# tedy.net
KiCad netlist of a schematic drawn in EAGLE
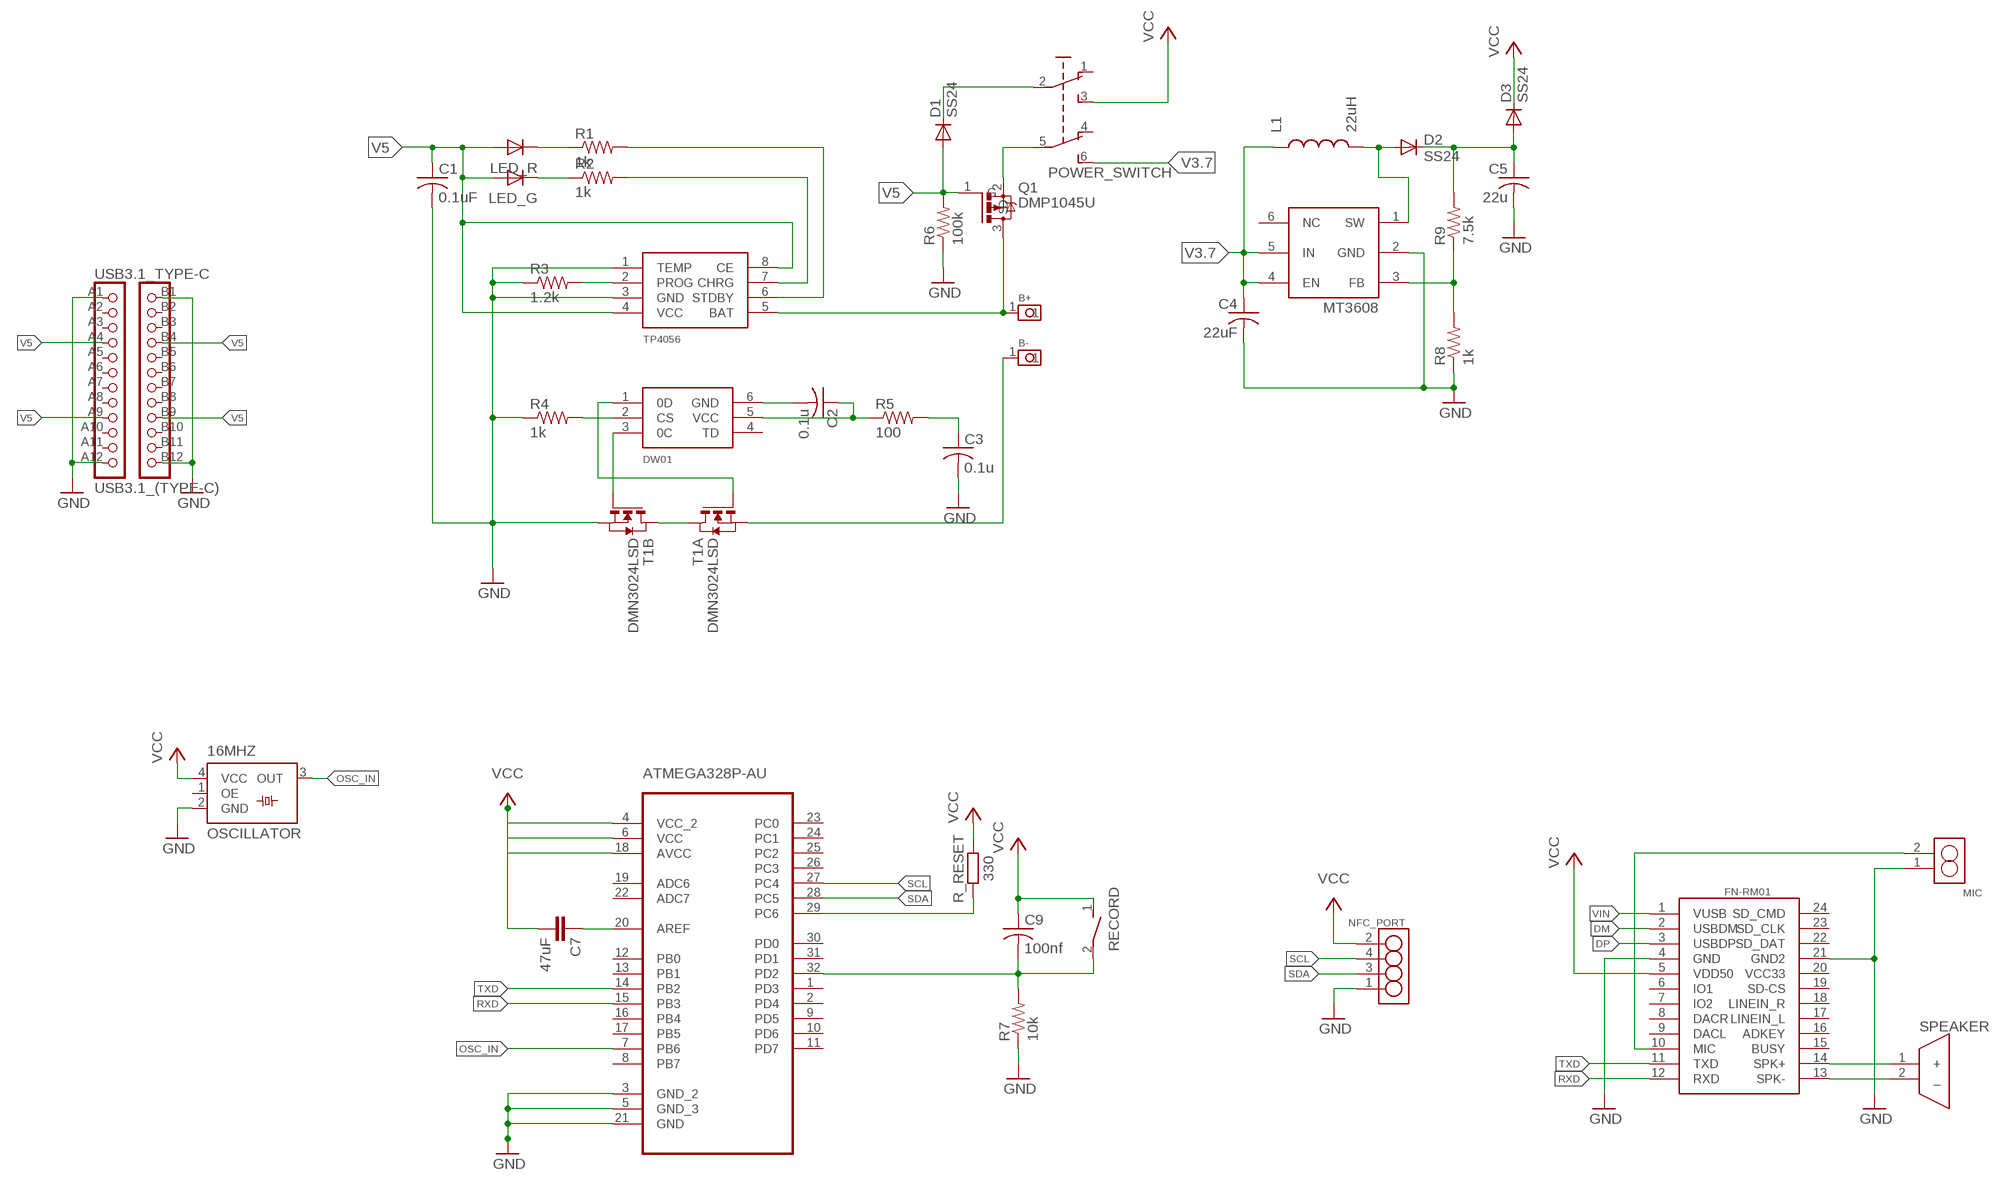
[diagram p0: schematic, sheet 1]

(export (version "E")
  (design (tool "Eeschema 10.0.6"))
  (components
    (comp (ref "16MHZ")
      (value "OSCILLATOR")
      (footprint "eagle-import:OSCILLATOR_(3.2_2.5)")
      (libsource (lib "eagle-import") (part "OSCILLATOR"))
    )
    (comp (ref "ATMEGA328P-AU")
      (value "ATMEGA328P-AU")
      (footprint "eagle-import:QFP80P900X900X120-32N")
      (libsource (lib "eagle-import") (part "ATMEGA328P-AU"))
    )
    (comp (ref "B+")
      (value "B+")
      (footprint "eagle-import:PIN_1")
      (libsource (lib "eagle-import") (part "PIN_1"))
    )
    (comp (ref "B-")
      (value "B-")
      (footprint "eagle-import:PIN_1")
      (libsource (lib "eagle-import") (part "PIN_1"))
    )
    (comp (ref "C1")
      (value "0.1uF")
      (footprint "eagle-import:C0805")
      (libsource (lib "eagle-import") (part "resistor_348_C-USC0805"))
    )
    (comp (ref "C2")
      (value "0.1u")
      (footprint "eagle-import:C0805")
      (libsource (lib "eagle-import") (part "resistor_348_C-USC0805"))
    )
    (comp (ref "C3")
      (value "0.1u")
      (footprint "eagle-import:C0805")
      (libsource (lib "eagle-import") (part "resistor_348_C-USC0805"))
    )
    (comp (ref "C4")
      (value "22uF")
      (footprint "eagle-import:C0805")
      (libsource (lib "eagle-import") (part "resistor_348_C-USC0805"))
    )
    (comp (ref "C5")
      (value "22u")
      (footprint "eagle-import:C0805")
      (libsource (lib "eagle-import") (part "resistor_348_C-USC0805"))
    )
    (comp (ref "C7")
      (value "47uF")
      (footprint "eagle-import:C0805")
      (libsource (lib "eagle-import") (part "C-EUC0805"))
    )
    (comp (ref "C9")
      (value "100nf")
      (footprint "eagle-import:C0805K")
      (libsource (lib "eagle-import") (part "C-USC0805K"))
    )
    (comp (ref "D1")
      (value "SS24")
      (footprint "eagle-import:SS24")
      (libsource (lib "eagle-import") (part "SS24"))
    )
    (comp (ref "D2")
      (value "SS24")
      (footprint "eagle-import:SS24")
      (libsource (lib "eagle-import") (part "SS24"))
    )
    (comp (ref "D3")
      (value "SS24")
      (footprint "eagle-import:SS24")
      (libsource (lib "eagle-import") (part "SS24"))
    )
    (comp (ref "DW01")
      (value "DW01")
      (footprint "eagle-import:SOT23-6")
      (libsource (lib "eagle-import") (part "DW01"))
    )
    (comp (ref "FN-RM01")
      (value "FN-RM01")
      (footprint "eagle-import:FN-RM01")
      (libsource (lib "eagle-import") (part "FN-RM01"))
    )
    (comp (ref "L1")
      (value "22uH")
      (footprint "eagle-import:4D28")
      (libsource (lib "eagle-import") (part "4D28"))
    )
    (comp (ref "LED_")
      (value "2_COLOUR_LED")
      (footprint "eagle-import:2_COLOUR_LED")
      (libsource (lib "eagle-import") (part "2_COLOUR_LED"))
    )
    (comp (ref "MIC")
      (value "CONNECTOR_1.5MM_THROUGH_HOLE_(2_PIN)")
      (footprint "eagle-import:CONNECTOR_1.5MM_THROUGH_HOLE_(2_PIN)")
      (libsource (lib "eagle-import") (part "CONNECTOR_1.5MM_THROUGH_HOLE_(2_PIN)"))
    )
    (comp (ref "MT3608")
      (value "MT3608")
      (footprint "eagle-import:SOT23-6")
      (libsource (lib "eagle-import") (part "MT3608"))
    )
    (comp (ref "NFC_PORT")
      (value "PN532")
      (footprint "eagle-import:PN532")
      (libsource (lib "eagle-import") (part "PN532"))
    )
    (comp (ref "POWER_SWITCH")
      (value "6PIN_SWITCH")
      (footprint "eagle-import:6PIN_SWITCH")
      (libsource (lib "eagle-import") (part "6PIN_SWITCH"))
    )
    (comp (ref "Q1")
      (value "DMP1045U")
      (footprint "eagle-import:SOT23-3")
      (libsource (lib "eagle-import") (part "DMP1045U"))
    )
    (comp (ref "R1")
      (value "1k")
      (footprint "eagle-import:R0805")
      (libsource (lib "eagle-import") (part "resistor_348_R-US_R0805"))
    )
    (comp (ref "R2")
      (value "1k")
      (footprint "eagle-import:R0805")
      (libsource (lib "eagle-import") (part "resistor_348_R-US_R0805"))
    )
    (comp (ref "R3")
      (value "1.2k")
      (footprint "eagle-import:R0805")
      (libsource (lib "eagle-import") (part "resistor_348_R-US_R0805"))
    )
    (comp (ref "R4")
      (value "1k")
      (footprint "eagle-import:R0805")
      (libsource (lib "eagle-import") (part "resistor_348_R-US_R0805"))
    )
    (comp (ref "R5")
      (value "100")
      (footprint "eagle-import:R0805")
      (libsource (lib "eagle-import") (part "resistor_348_R-US_R0805"))
    )
    (comp (ref "R6")
      (value "100k")
      (footprint "eagle-import:R0805")
      (libsource (lib "eagle-import") (part "resistor_348_R-US_R0805"))
    )
    (comp (ref "R7")
      (value "10k")
      (footprint "eagle-import:R0805")
      (libsource (lib "eagle-import") (part "R-US_R0805"))
    )
    (comp (ref "R8")
      (value "1k")
      (footprint "eagle-import:R0805")
      (libsource (lib "eagle-import") (part "resistor_348_R-US_R0805"))
    )
    (comp (ref "R9")
      (value "7.5k")
      (footprint "eagle-import:R0805")
      (libsource (lib "eagle-import") (part "resistor_348_R-US_R0805"))
    )
    (comp (ref "RECORD")
      (value "PUSH_BUTTON(SIDE)")
      (footprint "eagle-import:PUSH_BUTTON(SIDE)")
      (libsource (lib "eagle-import") (part "PUSH_BUTTON(SIDE)"))
    )
    (comp (ref "R_RESET")
      (value "330")
      (footprint "eagle-import:M0805")
      (libsource (lib "eagle-import") (part "R-EU_M0805"))
    )
    (comp (ref "SPEAKER")
      (value "SPEAKER")
      (footprint "eagle-import:SPEAKER")
      (libsource (lib "eagle-import") (part "SPEAKER"))
    )
    (comp (ref "T1")
      (value "DMN3024LSD")
      (footprint "eagle-import:TSSOP-8")
      (libsource (lib "eagle-import") (part "DMN3024LSD"))
    )
    (comp (ref "TP4056")
      (value "TP4056")
      (footprint "eagle-import:SOP-8")
      (libsource (lib "eagle-import") (part "TP4056"))
    )
    (comp (ref "USB3.1_TYPE-C")
      (value "USB3.1_(TYPE-C)")
      (footprint "eagle-import:USB3.1_(TYPE-C)")
      (libsource (lib "eagle-import") (part "USB3.1_(TYPE-C)"))
    )
  )
  (nets
    (net (code "1") (name "DM") (class "Default")
      (node (ref "FN-RM01") (pin "2") (pinfunction "USBDM_2") (pintype "bidirectional"))
    )
    (net (code "2") (name "DP") (class "Default")
      (node (ref "FN-RM01") (pin "3") (pinfunction "USBDP_3") (pintype "bidirectional"))
    )
    (net (code "3") (name "GND") (class "Default")
      (node (ref "16MHZ") (pin "2") (pinfunction "GND_2") (pintype "power_in"))
      (node (ref "ATMEGA328P-AU") (pin "21") (pinfunction "GND_21") (pintype "passive"))
      (node (ref "ATMEGA328P-AU") (pin "3") (pinfunction "GND_2_3") (pintype "passive"))
      (node (ref "ATMEGA328P-AU") (pin "5") (pinfunction "GND_3_5") (pintype "passive"))
      (node (ref "C1") (pin "2") (pinfunction "2_2") (pintype "passive"))
      (node (ref "C3") (pin "2") (pinfunction "2_2") (pintype "passive"))
      (node (ref "C4") (pin "2") (pinfunction "2_2") (pintype "passive"))
      (node (ref "C5") (pin "2") (pinfunction "2_2") (pintype "passive"))
      (node (ref "FN-RM01") (pin "21") (pinfunction "GND2_21") (pintype "bidirectional"))
      (node (ref "FN-RM01") (pin "4") (pinfunction "GND_4") (pintype "bidirectional"))
      (node (ref "MIC") (pin "1") (pinfunction "1_1") (pintype "bidirectional"))
      (node (ref "MT3608") (pin "2") (pinfunction "GND_2") (pintype "bidirectional"))
      (node (ref "NFC_PORT") (pin "1") (pinfunction "4_1") (pintype "bidirectional"))
      (node (ref "R3") (pin "1") (pinfunction "1_1") (pintype "passive"))
      (node (ref "R4") (pin "1") (pinfunction "1_1") (pintype "passive"))
      (node (ref "R6") (pin "1") (pinfunction "1_1") (pintype "passive"))
      (node (ref "R7") (pin "1") (pinfunction "1_1") (pintype "passive"))
      (node (ref "R8") (pin "1") (pinfunction "1_1") (pintype "passive"))
      (node (ref "T1") (pin "6") (pinfunction "S_6") (pintype "passive"))
      (node (ref "T1") (pin "7") (pinfunction "S_7") (pintype "passive"))
      (node (ref "TP4056") (pin "1") (pinfunction "TEMP_1") (pintype "bidirectional"))
      (node (ref "TP4056") (pin "3") (pinfunction "GND_3") (pintype "bidirectional"))
      (node (ref "USB3.1_TYPE-C") (pin "A1") (pinfunction "A1_A1") (pintype "passive"))
      (node (ref "USB3.1_TYPE-C") (pin "A12") (pinfunction "A12_A12") (pintype "passive"))
      (node (ref "USB3.1_TYPE-C") (pin "B1") (pinfunction "B1_B1") (pintype "passive"))
      (node (ref "USB3.1_TYPE-C") (pin "B12") (pinfunction "B12_B12") (pintype "passive"))
    )
    (net (code "4") (name "Net-(ATMEGA328P-AU-AREF)") (class "Default")
      (node (ref "ATMEGA328P-AU") (pin "20") (pinfunction "AREF_20") (pintype "input"))
      (node (ref "C7") (pin "1") (pinfunction "1_1") (pintype "passive"))
    )
    (net (code "5") (name "Net-(ATMEGA328P-AU-PC6)") (class "Default")
      (node (ref "ATMEGA328P-AU") (pin "29") (pinfunction "PC6_29") (pintype "bidirectional"))
      (node (ref "R_RESET") (pin "2") (pinfunction "2_2") (pintype "passive"))
    )
    (net (code "6") (name "Net-(ATMEGA328P-AU-PD2)") (class "Default")
      (node (ref "ATMEGA328P-AU") (pin "32") (pinfunction "PD2_32") (pintype "bidirectional"))
      (node (ref "C9") (pin "2") (pinfunction "2_2") (pintype "passive"))
      (node (ref "R7") (pin "2") (pinfunction "2_2") (pintype "passive"))
      (node (ref "RECORD") (pin "2") (pinfunction "2_2") (pintype "passive"))
    )
    (net (code "7") (name "Net-(B--Pad1)") (class "Default")
      (node (ref "B-") (pin "1") (pinfunction "1_1") (pintype "bidirectional"))
      (node (ref "T1") (pin "2") (pinfunction "S_2") (pintype "passive"))
      (node (ref "T1") (pin "3") (pinfunction "S_3") (pintype "passive"))
    )
    (net (code "8") (name "Net-(C3-Pad1)") (class "Default")
      (node (ref "C3") (pin "1") (pinfunction "1_1") (pintype "passive"))
      (node (ref "R5") (pin "2") (pinfunction "2_2") (pintype "passive"))
    )
    (net (code "9") (name "Net-(D1-C)") (class "Default")
      (node (ref "D1") (pin "2") (pinfunction "C_2") (pintype "passive"))
      (node (ref "POWER_SWITCH") (pin "2") (pinfunction "P_2") (pintype "passive"))
    )
    (net (code "10") (name "Net-(D2-A)") (class "Default")
      (node (ref "D2") (pin "1") (pinfunction "A_1") (pintype "passive"))
      (node (ref "L1") (pin "P$2") (pinfunction "2_P$2") (pintype "passive"))
      (node (ref "MT3608") (pin "1") (pinfunction "SW_1") (pintype "bidirectional"))
    )
    (net (code "11") (name "Net-(D2-C)") (class "Default")
      (node (ref "C5") (pin "1") (pinfunction "1_1") (pintype "passive"))
      (node (ref "D2") (pin "2") (pinfunction "C_2") (pintype "passive"))
      (node (ref "D3") (pin "1") (pinfunction "A_1") (pintype "passive"))
      (node (ref "R9") (pin "2") (pinfunction "2_2") (pintype "passive"))
    )
    (net (code "12") (name "Net-(DW01-0C)") (class "Default")
      (node (ref "DW01") (pin "3") (pinfunction "0C_3") (pintype "bidirectional"))
      (node (ref "T1") (pin "5") (pinfunction "G_5") (pintype "passive"))
    )
    (net (code "13") (name "Net-(DW01-0D)") (class "Default")
      (node (ref "DW01") (pin "1") (pinfunction "0D_1") (pintype "bidirectional"))
      (node (ref "T1") (pin "4") (pinfunction "G_4") (pintype "passive"))
    )
    (net (code "14") (name "Net-(DW01-CS)") (class "Default")
      (node (ref "DW01") (pin "2") (pinfunction "CS_2") (pintype "bidirectional"))
      (node (ref "R4") (pin "2") (pinfunction "2_2") (pintype "passive"))
    )
    (net (code "15") (name "Net-(DW01-GND)") (class "Default")
      (node (ref "C2") (pin "2") (pinfunction "2_2") (pintype "passive"))
      (node (ref "DW01") (pin "6") (pinfunction "GND_6") (pintype "bidirectional"))
    )
    (net (code "16") (name "Net-(DW01-VCC)") (class "Default")
      (node (ref "C2") (pin "1") (pinfunction "1_1") (pintype "passive"))
      (node (ref "DW01") (pin "5") (pinfunction "VCC_5") (pintype "bidirectional"))
      (node (ref "R5") (pin "1") (pinfunction "1_1") (pintype "passive"))
    )
    (net (code "17") (name "Net-(FN-RM01-MIC)") (class "Default")
      (node (ref "FN-RM01") (pin "10") (pinfunction "MIC_10") (pintype "bidirectional"))
      (node (ref "MIC") (pin "2") (pinfunction "2_2") (pintype "bidirectional"))
    )
    (net (code "18") (name "Net-(FN-RM01-SPK+)") (class "Default")
      (node (ref "FN-RM01") (pin "14") (pinfunction "SPK+_14") (pintype "bidirectional"))
      (node (ref "SPEAKER") (pin "1") (pinfunction "+_1") (pintype "bidirectional"))
    )
    (net (code "19") (name "Net-(FN-RM01-SPK-)") (class "Default")
      (node (ref "FN-RM01") (pin "13") (pinfunction "SPK-_13") (pintype "bidirectional"))
      (node (ref "SPEAKER") (pin "2") (pinfunction "__2") (pintype "bidirectional"))
    )
    (net (code "20") (name "Net-(LED_-Pad1)") (class "Default")
      (node (ref "LED_") (pin "1") (pinfunction "1_1") (pintype "passive"))
      (node (ref "R1") (pin "1") (pinfunction "1_1") (pintype "passive"))
    )
    (net (code "21") (name "Net-(LED_A-1)") (class "Default")
      (node (ref "LED_") (pin "3") (pinfunction "1_3") (pintype "passive"))
      (node (ref "R2") (pin "1") (pinfunction "1_1") (pintype "passive"))
    )
    (net (code "22") (name "Net-(MT3608-FB)") (class "Default")
      (node (ref "MT3608") (pin "3") (pinfunction "FB_3") (pintype "bidirectional"))
      (node (ref "R8") (pin "2") (pinfunction "2_2") (pintype "passive"))
      (node (ref "R9") (pin "1") (pinfunction "1_1") (pintype "passive"))
    )
    (net (code "23") (name "Net-(Q1-D)") (class "Default")
      (node (ref "B+") (pin "1") (pinfunction "1_1") (pintype "bidirectional"))
      (node (ref "Q1") (pin "3") (pinfunction "D_3") (pintype "bidirectional"))
      (node (ref "TP4056") (pin "5") (pinfunction "BAT_5") (pintype "bidirectional"))
    )
    (net (code "24") (name "Net-(T1A-D)") (class "Default")
      (node (ref "T1") (pin "1") (pinfunction "D_1") (pintype "passive"))
      (node (ref "T1") (pin "8") (pinfunction "D_8") (pintype "passive"))
    )
    (net (code "25") (name "Net-(TP4056-CHRG)") (class "Default")
      (node (ref "R2") (pin "2") (pinfunction "2_2") (pintype "passive"))
      (node (ref "TP4056") (pin "7") (pinfunction "CHRG_7") (pintype "bidirectional"))
    )
    (net (code "26") (name "Net-(TP4056-PROG)") (class "Default")
      (node (ref "R3") (pin "2") (pinfunction "2_2") (pintype "passive"))
      (node (ref "TP4056") (pin "2") (pinfunction "PROG_2") (pintype "bidirectional"))
    )
    (net (code "27") (name "Net-(TP4056-STDBY)") (class "Default")
      (node (ref "R1") (pin "2") (pinfunction "2_2") (pintype "passive"))
      (node (ref "TP4056") (pin "6") (pinfunction "STDBY_6") (pintype "bidirectional"))
    )
    (net (code "28") (name "OSC_IN") (class "Default")
      (node (ref "16MHZ") (pin "3") (pinfunction "OUT_3") (pintype "output"))
      (node (ref "ATMEGA328P-AU") (pin "7") (pinfunction "PB6_7") (pintype "bidirectional"))
    )
    (net (code "29") (name "RXD") (class "Default")
      (node (ref "ATMEGA328P-AU") (pin "15") (pinfunction "PB3_15") (pintype "bidirectional"))
      (node (ref "FN-RM01") (pin "12") (pinfunction "RXD_12") (pintype "bidirectional"))
    )
    (net (code "30") (name "SCL") (class "Default")
      (node (ref "ATMEGA328P-AU") (pin "27") (pinfunction "PC4_27") (pintype "bidirectional"))
      (node (ref "NFC_PORT") (pin "4") (pinfunction "2_4") (pintype "bidirectional"))
    )
    (net (code "31") (name "SDA") (class "Default")
      (node (ref "ATMEGA328P-AU") (pin "28") (pinfunction "PC5_28") (pintype "bidirectional"))
      (node (ref "NFC_PORT") (pin "3") (pinfunction "3_3") (pintype "bidirectional"))
    )
    (net (code "32") (name "TXD") (class "Default")
      (node (ref "ATMEGA328P-AU") (pin "14") (pinfunction "PB2_14") (pintype "bidirectional"))
      (node (ref "FN-RM01") (pin "11") (pinfunction "TXD_11") (pintype "bidirectional"))
    )
    (net (code "33") (name "V3.7") (class "Default")
      (node (ref "C4") (pin "1") (pinfunction "1_1") (pintype "passive"))
      (node (ref "L1") (pin "P$1") (pinfunction "1_P$1") (pintype "passive"))
      (node (ref "MT3608") (pin "4") (pinfunction "EN_4") (pintype "bidirectional"))
      (node (ref "MT3608") (pin "5") (pinfunction "IN_5") (pintype "bidirectional"))
      (node (ref "POWER_SWITCH") (pin "5") (pinfunction "P1_5") (pintype "passive"))
      (node (ref "POWER_SWITCH") (pin "6") (pinfunction "S1_6") (pintype "passive"))
      (node (ref "Q1") (pin "2") (pinfunction "S_2") (pintype "bidirectional"))
    )
    (net (code "34") (name "V5") (class "Default")
      (node (ref "C1") (pin "1") (pinfunction "1_1") (pintype "passive"))
      (node (ref "D1") (pin "1") (pinfunction "A_1") (pintype "passive"))
      (node (ref "LED_") (pin "2") (pinfunction "2_2") (pintype "passive"))
      (node (ref "LED_") (pin "4") (pinfunction "2_4") (pintype "passive"))
      (node (ref "Q1") (pin "1") (pinfunction "G_1") (pintype "bidirectional"))
      (node (ref "R6") (pin "2") (pinfunction "2_2") (pintype "passive"))
      (node (ref "TP4056") (pin "4") (pinfunction "VCC_4") (pintype "bidirectional"))
      (node (ref "TP4056") (pin "8") (pinfunction "CE_8") (pintype "bidirectional"))
      (node (ref "USB3.1_TYPE-C") (pin "A4") (pinfunction "A4_A4") (pintype "passive"))
      (node (ref "USB3.1_TYPE-C") (pin "A9") (pinfunction "A9_A9") (pintype "passive"))
      (node (ref "USB3.1_TYPE-C") (pin "B4") (pinfunction "B4_B4") (pintype "passive"))
      (node (ref "USB3.1_TYPE-C") (pin "B9") (pinfunction "B9_B9") (pintype "passive"))
    )
    (net (code "35") (name "VCC") (class "Default")
      (node (ref "16MHZ") (pin "4") (pinfunction "VCC_4") (pintype "power_in"))
      (node (ref "ATMEGA328P-AU") (pin "18") (pinfunction "AVCC_18") (pintype "power_in"))
      (node (ref "ATMEGA328P-AU") (pin "4") (pinfunction "VCC_2_4") (pintype "power_in"))
      (node (ref "ATMEGA328P-AU") (pin "6") (pinfunction "VCC_6") (pintype "power_in"))
      (node (ref "C7") (pin "2") (pinfunction "2_2") (pintype "passive"))
      (node (ref "C9") (pin "1") (pinfunction "1_1") (pintype "passive"))
      (node (ref "D3") (pin "2") (pinfunction "C_2") (pintype "passive"))
      (node (ref "FN-RM01") (pin "5") (pinfunction "VDD50_5") (pintype "bidirectional"))
      (node (ref "NFC_PORT") (pin "2") (pinfunction "1_2") (pintype "bidirectional"))
      (node (ref "POWER_SWITCH") (pin "3") (pinfunction "S_3") (pintype "passive"))
      (node (ref "RECORD") (pin "1") (pinfunction "1_1") (pintype "passive"))
      (node (ref "R_RESET") (pin "1") (pinfunction "1_1") (pintype "passive"))
    )
    (net (code "36") (name "VIN") (class "Default")
      (node (ref "FN-RM01") (pin "1") (pinfunction "VUSB_1") (pintype "bidirectional"))
    )
    (net (code "37") (name "unconnected-(16MHZ-OE-Pad1)") (class "Default")
      (node (ref "16MHZ") (pin "1") (pinfunction "OE_1") (pintype "input"))
    )
    (net (code "38") (name "unconnected-(ATMEGA328P-AU-ADC6-Pad19)") (class "Default")
      (node (ref "ATMEGA328P-AU") (pin "19") (pinfunction "ADC6_19") (pintype "input"))
    )
    (net (code "39") (name "unconnected-(ATMEGA328P-AU-ADC7-Pad22)") (class "Default")
      (node (ref "ATMEGA328P-AU") (pin "22") (pinfunction "ADC7_22") (pintype "input"))
    )
    (net (code "40") (name "unconnected-(ATMEGA328P-AU-PB0-Pad12)") (class "Default")
      (node (ref "ATMEGA328P-AU") (pin "12") (pinfunction "PB0_12") (pintype "bidirectional"))
    )
    (net (code "41") (name "unconnected-(ATMEGA328P-AU-PB1-Pad13)") (class "Default")
      (node (ref "ATMEGA328P-AU") (pin "13") (pinfunction "PB1_13") (pintype "bidirectional"))
    )
    (net (code "42") (name "unconnected-(ATMEGA328P-AU-PB4-Pad16)") (class "Default")
      (node (ref "ATMEGA328P-AU") (pin "16") (pinfunction "PB4_16") (pintype "bidirectional"))
    )
    (net (code "43") (name "unconnected-(ATMEGA328P-AU-PB5-Pad17)") (class "Default")
      (node (ref "ATMEGA328P-AU") (pin "17") (pinfunction "PB5_17") (pintype "bidirectional"))
    )
    (net (code "44") (name "unconnected-(ATMEGA328P-AU-PB7-Pad8)") (class "Default")
      (node (ref "ATMEGA328P-AU") (pin "8") (pinfunction "PB7_8") (pintype "bidirectional"))
    )
    (net (code "45") (name "unconnected-(ATMEGA328P-AU-PC0-Pad23)") (class "Default")
      (node (ref "ATMEGA328P-AU") (pin "23") (pinfunction "PC0_23") (pintype "bidirectional"))
    )
    (net (code "46") (name "unconnected-(ATMEGA328P-AU-PC1-Pad24)") (class "Default")
      (node (ref "ATMEGA328P-AU") (pin "24") (pinfunction "PC1_24") (pintype "bidirectional"))
    )
    (net (code "47") (name "unconnected-(ATMEGA328P-AU-PC2-Pad25)") (class "Default")
      (node (ref "ATMEGA328P-AU") (pin "25") (pinfunction "PC2_25") (pintype "bidirectional"))
    )
    (net (code "48") (name "unconnected-(ATMEGA328P-AU-PC3-Pad26)") (class "Default")
      (node (ref "ATMEGA328P-AU") (pin "26") (pinfunction "PC3_26") (pintype "bidirectional"))
    )
    (net (code "49") (name "unconnected-(ATMEGA328P-AU-PD0-Pad30)") (class "Default")
      (node (ref "ATMEGA328P-AU") (pin "30") (pinfunction "PD0_30") (pintype "bidirectional"))
    )
    (net (code "50") (name "unconnected-(ATMEGA328P-AU-PD1-Pad31)") (class "Default")
      (node (ref "ATMEGA328P-AU") (pin "31") (pinfunction "PD1_31") (pintype "bidirectional"))
    )
    (net (code "51") (name "unconnected-(ATMEGA328P-AU-PD3-Pad1)") (class "Default")
      (node (ref "ATMEGA328P-AU") (pin "1") (pinfunction "PD3_1") (pintype "bidirectional"))
    )
    (net (code "52") (name "unconnected-(ATMEGA328P-AU-PD4-Pad2)") (class "Default")
      (node (ref "ATMEGA328P-AU") (pin "2") (pinfunction "PD4_2") (pintype "bidirectional"))
    )
    (net (code "53") (name "unconnected-(ATMEGA328P-AU-PD5-Pad9)") (class "Default")
      (node (ref "ATMEGA328P-AU") (pin "9") (pinfunction "PD5_9") (pintype "bidirectional"))
    )
    (net (code "54") (name "unconnected-(ATMEGA328P-AU-PD6-Pad10)") (class "Default")
      (node (ref "ATMEGA328P-AU") (pin "10") (pinfunction "PD6_10") (pintype "bidirectional"))
    )
    (net (code "55") (name "unconnected-(ATMEGA328P-AU-PD7-Pad11)") (class "Default")
      (node (ref "ATMEGA328P-AU") (pin "11") (pinfunction "PD7_11") (pintype "bidirectional"))
    )
    (net (code "56") (name "unconnected-(DW01-TD-Pad4)") (class "Default")
      (node (ref "DW01") (pin "4") (pinfunction "TD_4") (pintype "bidirectional"))
    )
    (net (code "57") (name "unconnected-(FN-RM01-ADKEY-Pad16)") (class "Default")
      (node (ref "FN-RM01") (pin "16") (pinfunction "ADKEY_16") (pintype "bidirectional"))
    )
    (net (code "58") (name "unconnected-(FN-RM01-BUSY-Pad15)") (class "Default")
      (node (ref "FN-RM01") (pin "15") (pinfunction "BUSY_15") (pintype "bidirectional"))
    )
    (net (code "59") (name "unconnected-(FN-RM01-DACL-Pad9)") (class "Default")
      (node (ref "FN-RM01") (pin "9") (pinfunction "DACL_9") (pintype "bidirectional"))
    )
    (net (code "60") (name "unconnected-(FN-RM01-DACR-Pad8)") (class "Default")
      (node (ref "FN-RM01") (pin "8") (pinfunction "DACR_8") (pintype "bidirectional"))
    )
    (net (code "61") (name "unconnected-(FN-RM01-IO1-Pad6)") (class "Default")
      (node (ref "FN-RM01") (pin "6") (pinfunction "IO1_6") (pintype "bidirectional"))
    )
    (net (code "62") (name "unconnected-(FN-RM01-IO2-Pad7)") (class "Default")
      (node (ref "FN-RM01") (pin "7") (pinfunction "IO2_7") (pintype "bidirectional"))
    )
    (net (code "63") (name "unconnected-(FN-RM01-LINEIN_L-Pad17)") (class "Default")
      (node (ref "FN-RM01") (pin "17") (pinfunction "LINEIN_L_17") (pintype "bidirectional"))
    )
    (net (code "64") (name "unconnected-(FN-RM01-LINEIN_R-Pad18)") (class "Default")
      (node (ref "FN-RM01") (pin "18") (pinfunction "LINEIN_R_18") (pintype "bidirectional"))
    )
    (net (code "65") (name "unconnected-(FN-RM01-SD-CS-Pad19)") (class "Default")
      (node (ref "FN-RM01") (pin "19") (pinfunction "SD-CS_19") (pintype "bidirectional"))
    )
    (net (code "66") (name "unconnected-(FN-RM01-SD_CLK-Pad23)") (class "Default")
      (node (ref "FN-RM01") (pin "23") (pinfunction "SD_CLK_23") (pintype "bidirectional"))
    )
    (net (code "67") (name "unconnected-(FN-RM01-SD_CMD-Pad24)") (class "Default")
      (node (ref "FN-RM01") (pin "24") (pinfunction "SD_CMD_24") (pintype "bidirectional"))
    )
    (net (code "68") (name "unconnected-(FN-RM01-SD_DAT-Pad22)") (class "Default")
      (node (ref "FN-RM01") (pin "22") (pinfunction "SD_DAT_22") (pintype "bidirectional"))
    )
    (net (code "69") (name "unconnected-(FN-RM01-VCC33-Pad20)") (class "Default")
      (node (ref "FN-RM01") (pin "20") (pinfunction "VCC33_20") (pintype "bidirectional"))
    )
    (net (code "70") (name "unconnected-(MT3608-NC-Pad6)") (class "Default")
      (node (ref "MT3608") (pin "6") (pinfunction "NC_6") (pintype "bidirectional"))
    )
    (net (code "71") (name "unconnected-(POWER_SWITCH-O-Pad1)") (class "Default")
      (node (ref "POWER_SWITCH") (pin "1") (pinfunction "O_1") (pintype "passive"))
    )
    (net (code "72") (name "unconnected-(POWER_SWITCH-O1-Pad4)") (class "Default")
      (node (ref "POWER_SWITCH") (pin "4") (pinfunction "O1_4") (pintype "passive"))
    )
    (net (code "73") (name "unconnected-(USB3.1_TYPE-C-PadA2)") (class "Default")
      (node (ref "USB3.1_TYPE-C") (pin "A2") (pinfunction "A2_A2") (pintype "passive"))
    )
    (net (code "74") (name "unconnected-(USB3.1_TYPE-C-PadA3)") (class "Default")
      (node (ref "USB3.1_TYPE-C") (pin "A3") (pinfunction "A3_A3") (pintype "passive"))
    )
    (net (code "75") (name "unconnected-(USB3.1_TYPE-C-PadA5)") (class "Default")
      (node (ref "USB3.1_TYPE-C") (pin "A5") (pinfunction "A5_A5") (pintype "passive"))
    )
    (net (code "76") (name "unconnected-(USB3.1_TYPE-C-PadA6)") (class "Default")
      (node (ref "USB3.1_TYPE-C") (pin "A6") (pinfunction "A6_A6") (pintype "passive"))
    )
    (net (code "77") (name "unconnected-(USB3.1_TYPE-C-PadA7)") (class "Default")
      (node (ref "USB3.1_TYPE-C") (pin "A7") (pinfunction "A7_A7") (pintype "passive"))
    )
    (net (code "78") (name "unconnected-(USB3.1_TYPE-C-PadA8)") (class "Default")
      (node (ref "USB3.1_TYPE-C") (pin "A8") (pinfunction "A8_A8") (pintype "passive"))
    )
    (net (code "79") (name "unconnected-(USB3.1_TYPE-C-PadA10)") (class "Default")
      (node (ref "USB3.1_TYPE-C") (pin "A10") (pinfunction "A10_A10") (pintype "passive"))
    )
    (net (code "80") (name "unconnected-(USB3.1_TYPE-C-PadA11)") (class "Default")
      (node (ref "USB3.1_TYPE-C") (pin "A11") (pinfunction "A11_A11") (pintype "passive"))
    )
    (net (code "81") (name "unconnected-(USB3.1_TYPE-C-PadB2)") (class "Default")
      (node (ref "USB3.1_TYPE-C") (pin "B2") (pinfunction "B2_B2") (pintype "passive"))
    )
    (net (code "82") (name "unconnected-(USB3.1_TYPE-C-PadB3)") (class "Default")
      (node (ref "USB3.1_TYPE-C") (pin "B3") (pinfunction "B3_B3") (pintype "passive"))
    )
    (net (code "83") (name "unconnected-(USB3.1_TYPE-C-PadB5)") (class "Default")
      (node (ref "USB3.1_TYPE-C") (pin "B5") (pinfunction "B5_B5") (pintype "passive"))
    )
    (net (code "84") (name "unconnected-(USB3.1_TYPE-C-PadB6)") (class "Default")
      (node (ref "USB3.1_TYPE-C") (pin "B6") (pinfunction "B6_B6") (pintype "passive"))
    )
    (net (code "85") (name "unconnected-(USB3.1_TYPE-C-PadB7)") (class "Default")
      (node (ref "USB3.1_TYPE-C") (pin "B7") (pinfunction "B7_B7") (pintype "passive"))
    )
    (net (code "86") (name "unconnected-(USB3.1_TYPE-C-PadB8)") (class "Default")
      (node (ref "USB3.1_TYPE-C") (pin "B8") (pinfunction "B8_B8") (pintype "passive"))
    )
    (net (code "87") (name "unconnected-(USB3.1_TYPE-C-PadB10)") (class "Default")
      (node (ref "USB3.1_TYPE-C") (pin "B10") (pinfunction "B10_B10") (pintype "passive"))
    )
    (net (code "88") (name "unconnected-(USB3.1_TYPE-C-PadB11)") (class "Default")
      (node (ref "USB3.1_TYPE-C") (pin "B11") (pinfunction "B11_B11") (pintype "passive"))
    )
  )
)
